# SCH_ECD_Project_Group_08_2025-03-04.net
KiCad netlist of a schematic drawn in EasyEDA
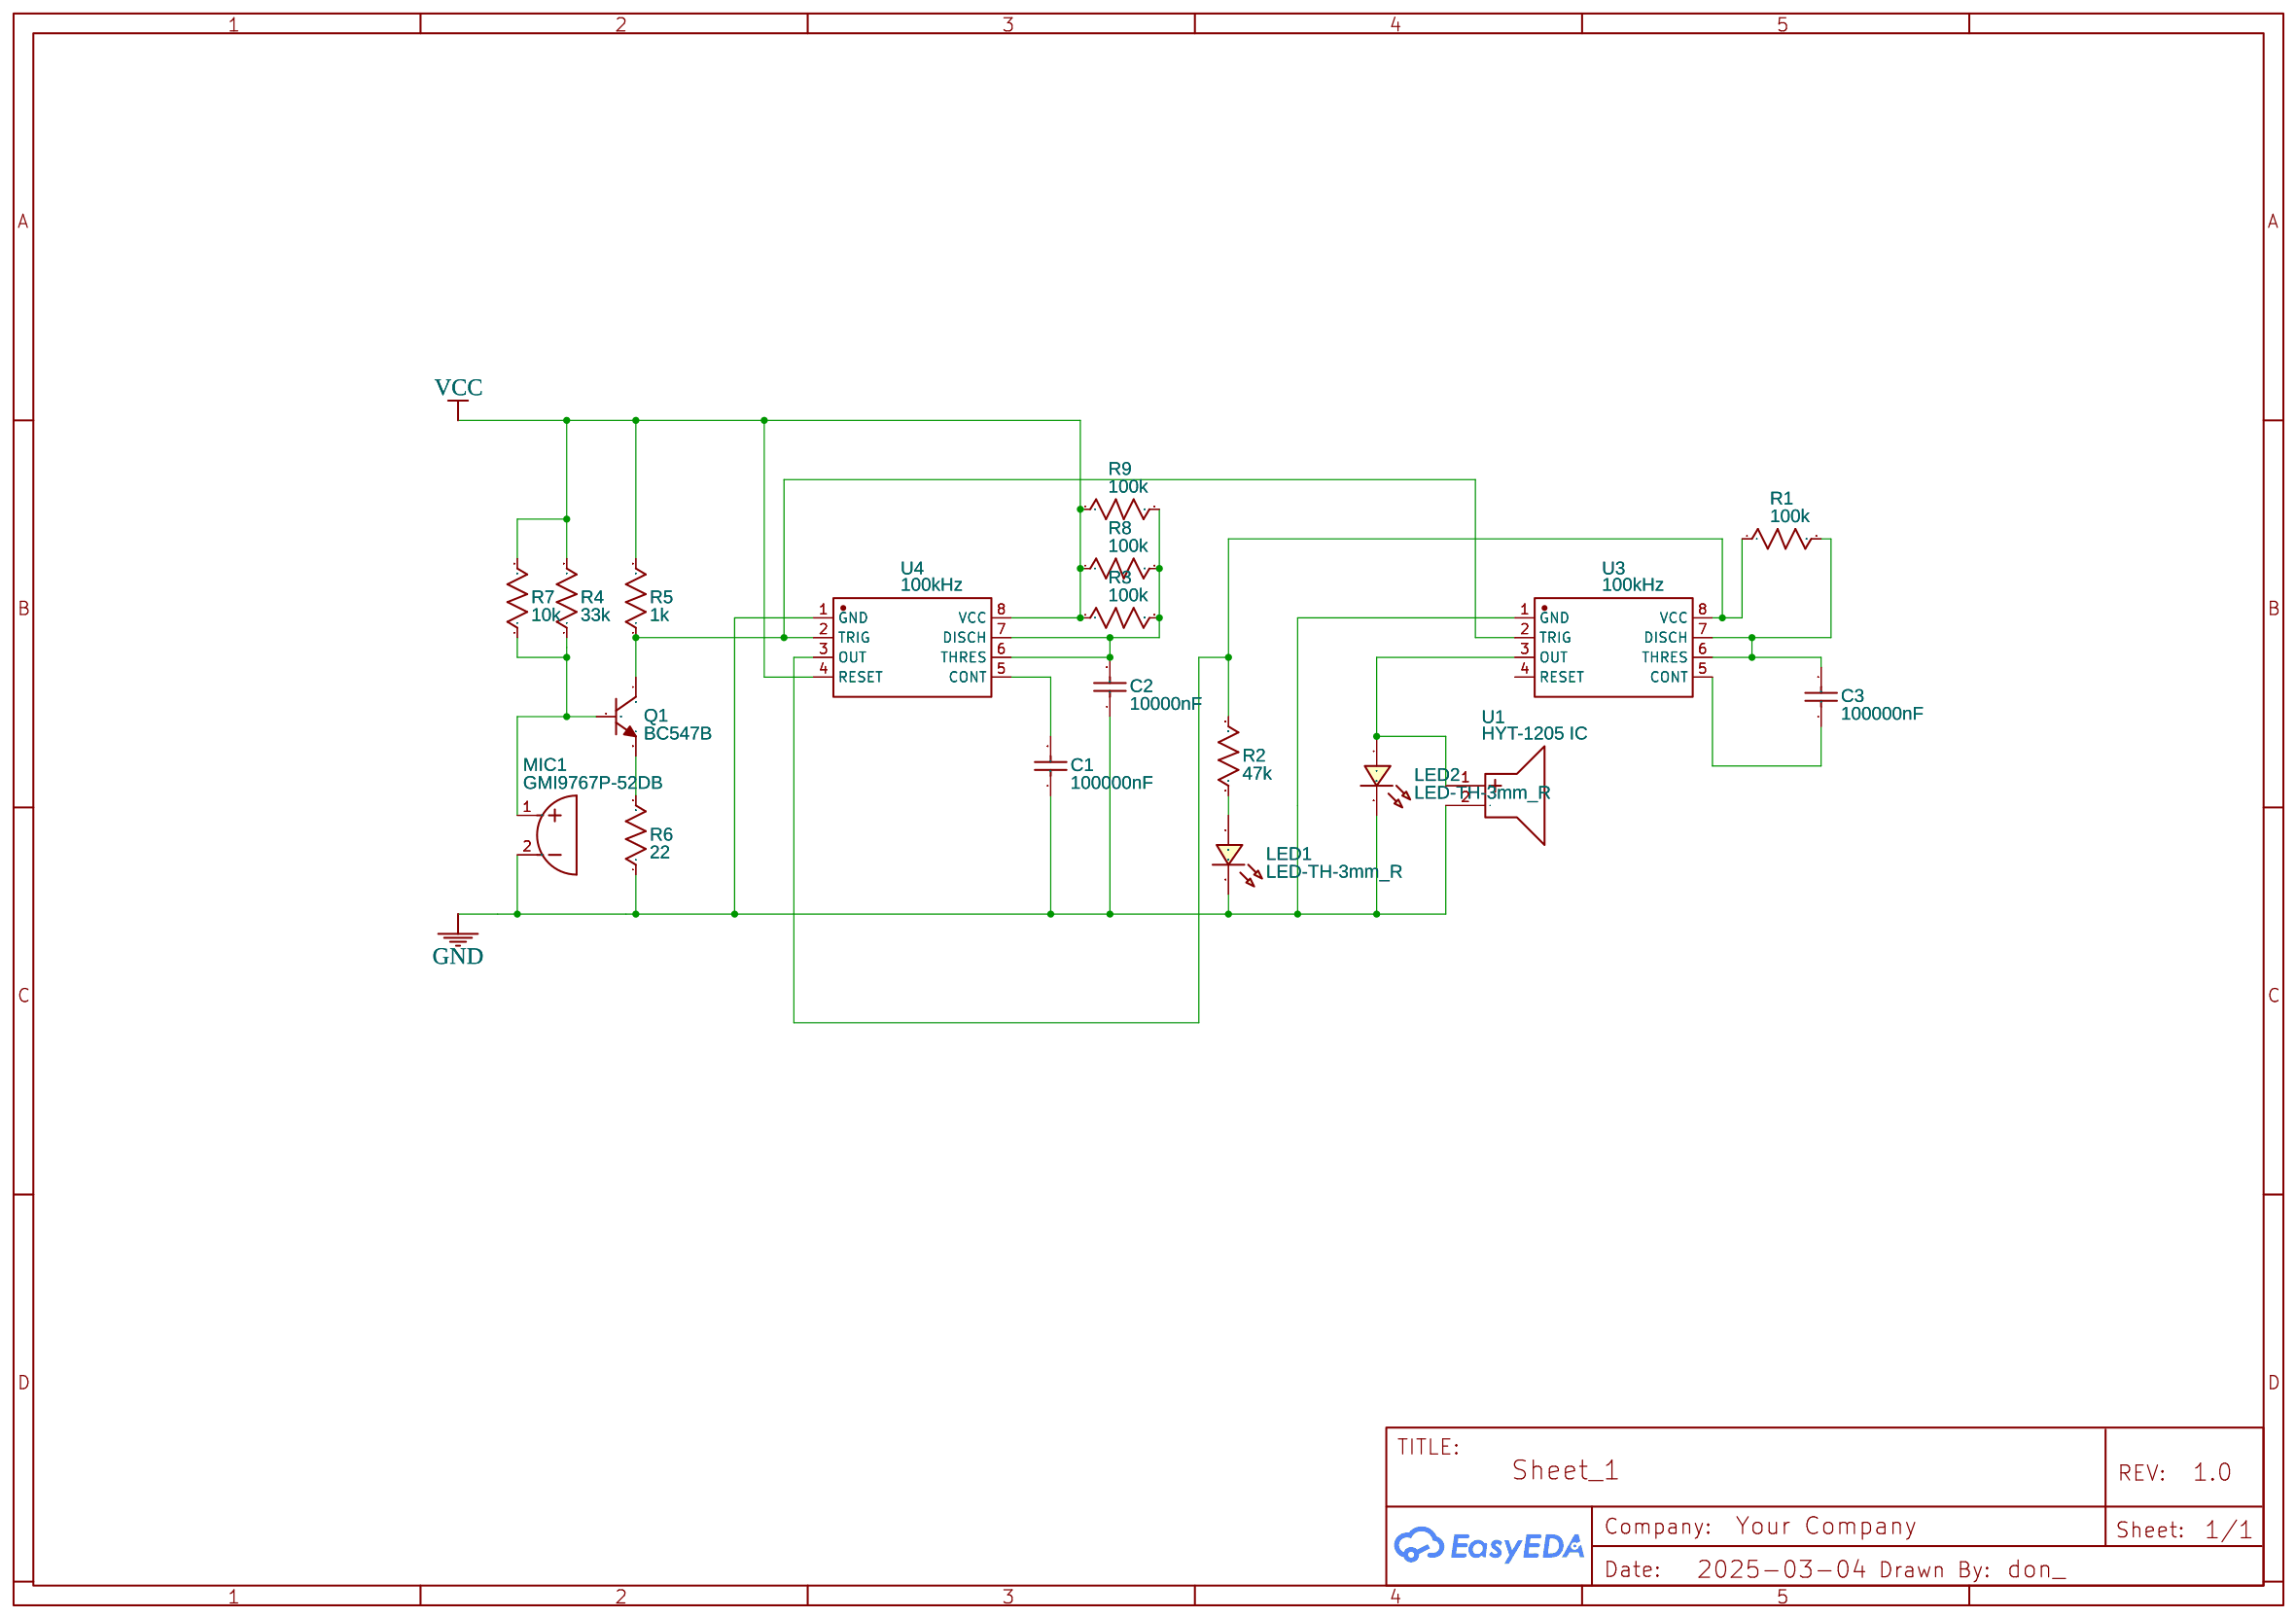
[diagram p0: schematic sheet]

(export (version "E")
  (design (tool "Eeschema 10.0.6"))
  (components
    (comp (ref "C1")
      (value "100000nF")
      (fields (field (name "Manufacturer Part") "电容15nf100v"))
      (libsource (lib "") (part "CAPACITOR15NF100V"))
    )
    (comp (ref "C2")
      (value "10000nF")
      (fields (field (name "Manufacturer Part") "电容15nf100v"))
      (libsource (lib "") (part "CAPACITOR15NF100V"))
    )
    (comp (ref "C3")
      (value "100000nF")
      (fields (field (name "Manufacturer Part") "电容15nf100v"))
      (libsource (lib "") (part "CAPACITOR15NF100V"))
    )
    (comp (ref "LED1")
      (value "LED-TH-3mm_R")
      (fields
        (field (name "Manufacturer Part") "204-10SDRD/S530-A3-L")
        (field (name "Manufacturer") "EVERLIGHT(台湾亿光)")
      )
      (libsource (lib "") (part "LED-TH-3mm_R"))
    )
    (comp (ref "LED2")
      (value "LED-TH-3mm_R")
      (fields
        (field (name "Manufacturer Part") "204-10SDRD/S530-A3-L")
        (field (name "Manufacturer") "EVERLIGHT(台湾亿光)")
      )
      (libsource (lib "") (part "LED-TH-3mm_R"))
    )
    (comp (ref "MIC1")
      (value "GMI9767P-52DB")
      (fields (field (name "Manufacturer") "INGHAi(赢海)"))
      (libsource (lib "") (part "GMI9767P-52DB"))
    )
    (comp (ref "Q1")
      (value "BC547B")
      (fields (field (name "Manufacturer") "LGE(鲁光)"))
      (libsource (lib "") (part "BC547B"))
    )
    (comp (ref "R1") (value "100k") (libsource (lib "") (part "R_AXIAL-0.4_US_1")))
    (comp (ref "R2") (value "47k") (libsource (lib "") (part "R_AXIAL-0.4_US")))
    (comp (ref "R3") (value "100k") (libsource (lib "") (part "R_AXIAL-0.4_US_1")))
    (comp (ref "R4") (value "33k") (libsource (lib "") (part "R_AXIAL-0.4_US")))
    (comp (ref "R5") (value "1k") (libsource (lib "") (part "R_AXIAL-0.4_US")))
    (comp (ref "R6") (value "22") (libsource (lib "") (part "R_AXIAL-0.4_US")))
    (comp (ref "R7") (value "10k") (libsource (lib "") (part "R_AXIAL-0.4_US")))
    (comp (ref "R8") (value "100k") (libsource (lib "") (part "R_AXIAL-0.4_US_1")))
    (comp (ref "R9") (value "100k") (libsource (lib "") (part "R_AXIAL-0.4_US_1")))
    (comp (ref "U1")
      (value "HYT-1205 IC")
      (fields (field (name "Manufacturer") "HYDZ(华宇)"))
      (libsource (lib "") (part "HYT-1205 IC"))
    )
    (comp (ref "U3")
      (value "100kHz")
      (fields (field (name "Manufacturer Part") "NA555P") (field (name "Manufacturer") "TI(德州仪器)"))
      (libsource (lib "") (part "NA555P"))
    )
    (comp (ref "U4")
      (value "100kHz")
      (fields (field (name "Manufacturer Part") "NA555P") (field (name "Manufacturer") "TI(德州仪器)"))
      (libsource (lib "") (part "NA555P"))
    )
  )
  (nets
    (net (code "1") (name "GND") (class "Default")
      (node (ref "C1") (pin "1") (pinfunction "1_1") (pintype "input"))
      (node (ref "C2") (pin "1") (pinfunction "1_1") (pintype "input"))
      (node (ref "LED1") (pin "2") (pinfunction "2_2") (pintype "unspecified"))
      (node (ref "LED2") (pin "2") (pinfunction "2_2") (pintype "unspecified"))
      (node (ref "MIC1") (pin "2") (pinfunction "2_2") (pintype "unspecified"))
      (node (ref "R6") (pin "1") (pinfunction "1_1") (pintype "unspecified"))
      (node (ref "U1") (pin "2") (pinfunction "-_2") (pintype "unspecified"))
      (node (ref "U3") (pin "1") (pinfunction "GND_1") (pintype "unspecified"))
      (node (ref "U4") (pin "1") (pinfunction "GND_1") (pintype "unspecified"))
    )
    (net (code "2") (name "Net-(LED1-Pad1)") (class "Default")
      (node (ref "LED1") (pin "1") (pinfunction "1_1") (pintype "unspecified"))
      (node (ref "R2") (pin "1") (pinfunction "1_1") (pintype "unspecified"))
    )
    (net (code "3") (name "Net-(Q1-B)") (class "Default")
      (node (ref "MIC1") (pin "1") (pinfunction "1_1") (pintype "unspecified"))
      (node (ref "Q1") (pin "2") (pinfunction "B_2") (pintype "input"))
      (node (ref "R4") (pin "1") (pinfunction "1_1") (pintype "unspecified"))
      (node (ref "R7") (pin "1") (pinfunction "1_1") (pintype "unspecified"))
    )
    (net (code "4") (name "Net-(Q1-C)") (class "Default")
      (node (ref "Q1") (pin "1") (pinfunction "C_1") (pintype "input"))
      (node (ref "R5") (pin "1") (pinfunction "1_1") (pintype "unspecified"))
      (node (ref "U3") (pin "2") (pinfunction "TRIG_2") (pintype "unspecified"))
      (node (ref "U4") (pin "2") (pinfunction "TRIG_2") (pintype "unspecified"))
    )
    (net (code "5") (name "Net-(Q1-E)") (class "Default")
      (node (ref "Q1") (pin "3") (pinfunction "E_3") (pintype "input"))
      (node (ref "R6") (pin "2") (pinfunction "2_2") (pintype "unspecified"))
    )
    (net (code "6") (name "Net-(U1-+)") (class "Default")
      (node (ref "LED2") (pin "1") (pinfunction "1_1") (pintype "unspecified"))
      (node (ref "U1") (pin "1") (pinfunction "+_1") (pintype "unspecified"))
      (node (ref "U3") (pin "3") (pinfunction "OUT_3") (pintype "unspecified"))
    )
    (net (code "7") (name "Net-(U3-CONT)") (class "Default")
      (node (ref "C3") (pin "1") (pinfunction "1_1") (pintype "input"))
      (node (ref "U3") (pin "5") (pinfunction "CONT_5") (pintype "unspecified"))
    )
    (net (code "8") (name "Net-(U3-DISCH)") (class "Default")
      (node (ref "C3") (pin "2") (pinfunction "2_2") (pintype "input"))
      (node (ref "R1") (pin "2") (pinfunction "2_2") (pintype "unspecified"))
      (node (ref "U3") (pin "6") (pinfunction "THRES_6") (pintype "unspecified"))
      (node (ref "U3") (pin "7") (pinfunction "DISCH_7") (pintype "unspecified"))
    )
    (net (code "9") (name "Net-(U3-VCC)") (class "Default")
      (node (ref "R1") (pin "1") (pinfunction "1_1") (pintype "unspecified"))
      (node (ref "R2") (pin "2") (pinfunction "2_2") (pintype "unspecified"))
      (node (ref "U3") (pin "8") (pinfunction "VCC_8") (pintype "unspecified"))
      (node (ref "U4") (pin "3") (pinfunction "OUT_3") (pintype "unspecified"))
    )
    (net (code "10") (name "Net-(U4-CONT)") (class "Default")
      (node (ref "C1") (pin "2") (pinfunction "2_2") (pintype "input"))
      (node (ref "U4") (pin "5") (pinfunction "CONT_5") (pintype "unspecified"))
    )
    (net (code "11") (name "Net-(U4-DISCH)") (class "Default")
      (node (ref "C2") (pin "2") (pinfunction "2_2") (pintype "input"))
      (node (ref "R3") (pin "2") (pinfunction "2_2") (pintype "unspecified"))
      (node (ref "R8") (pin "2") (pinfunction "2_2") (pintype "unspecified"))
      (node (ref "R9") (pin "2") (pinfunction "2_2") (pintype "unspecified"))
      (node (ref "U4") (pin "6") (pinfunction "THRES_6") (pintype "unspecified"))
      (node (ref "U4") (pin "7") (pinfunction "DISCH_7") (pintype "unspecified"))
    )
    (net (code "12") (name "VCC") (class "Default")
      (node (ref "R3") (pin "1") (pinfunction "1_1") (pintype "unspecified"))
      (node (ref "R4") (pin "2") (pinfunction "2_2") (pintype "unspecified"))
      (node (ref "R5") (pin "2") (pinfunction "2_2") (pintype "unspecified"))
      (node (ref "R7") (pin "2") (pinfunction "2_2") (pintype "unspecified"))
      (node (ref "R8") (pin "1") (pinfunction "1_1") (pintype "unspecified"))
      (node (ref "R9") (pin "1") (pinfunction "1_1") (pintype "unspecified"))
      (node (ref "U4") (pin "4") (pinfunction "RESET_4") (pintype "unspecified"))
      (node (ref "U4") (pin "8") (pinfunction "VCC_8") (pintype "unspecified"))
    )
    (net (code "13") (name "unconnected-(U3-RESET-Pad4)") (class "Default")
      (node (ref "U3") (pin "4") (pinfunction "RESET_4") (pintype "unspecified"))
    )
  )
)
